# PCB.net
KiCad netlist of a schematic drawn in EAGLE
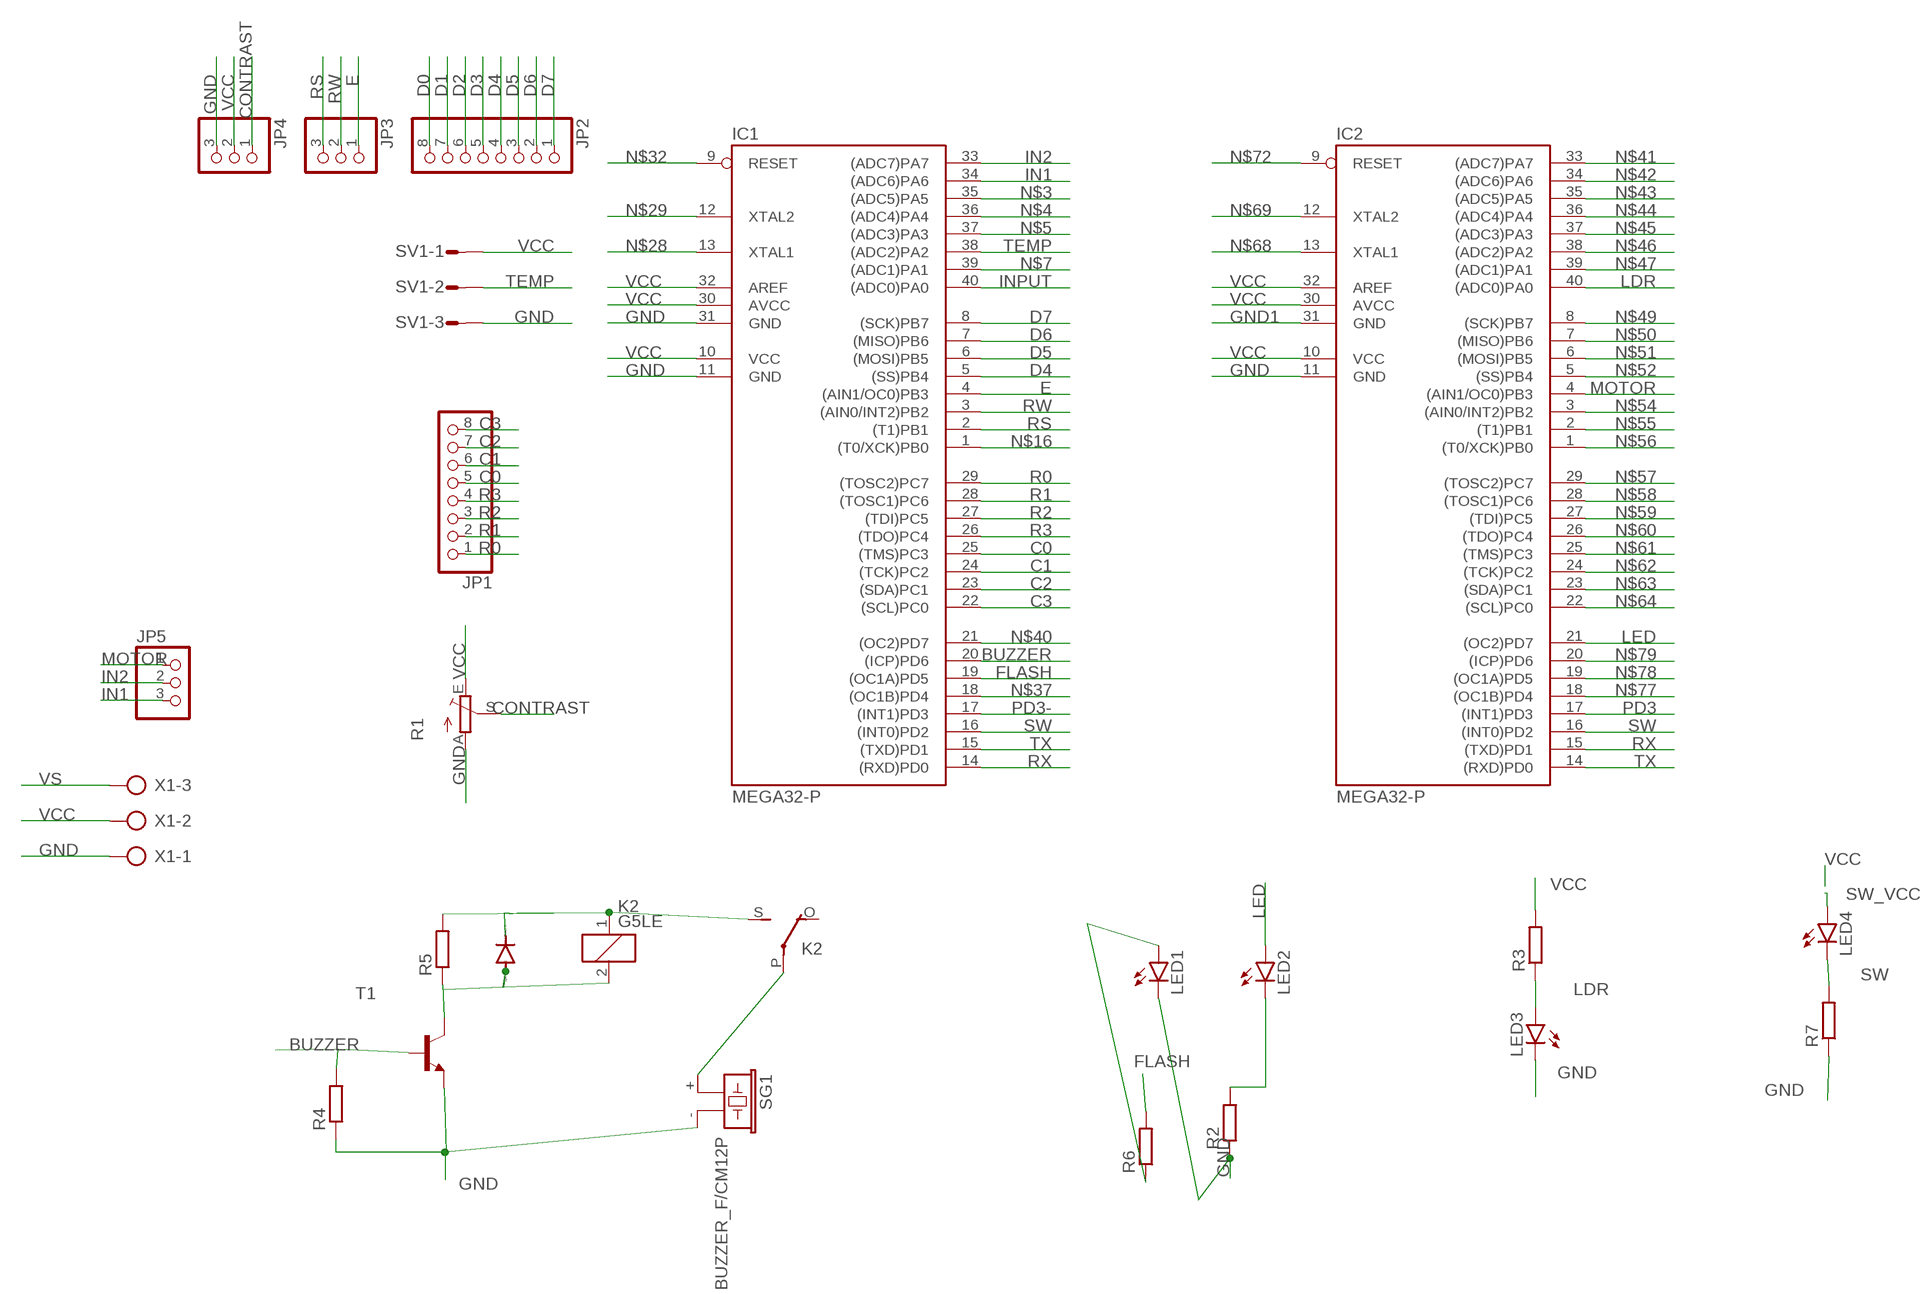
[diagram p0: schematic, sheet 1]

(export (version "E")
  (design (tool "Eeschema 10.0.6"))
  (components
    (comp (ref "D1")
      (value "1N4004")
      (footprint "eagle-import:DO41-10")
      (libsource (lib "eagle-import") (part "1N4004"))
    )
    (comp (ref "IC1")
      (value "MEGA32-P")
      (footprint "eagle-import:DIL40")
      (fields (field (name "MPN") "ATMEGA32-16PU"))
      (libsource (lib "eagle-import") (part "MEGA32-P"))
    )
    (comp (ref "IC2")
      (value "MEGA32-P")
      (footprint "eagle-import:DIL40")
      (fields (field (name "MPN") "ATMEGA32-16PU"))
      (libsource (lib "eagle-import") (part "MEGA32-P"))
    )
    (comp (ref "JP1")
      (value "PINHD-1X8")
      (footprint "eagle-import:1X08")
      (libsource (lib "eagle-import") (part "PINHD-1X8"))
    )
    (comp (ref "JP2")
      (value "PINHD-1X8")
      (footprint "eagle-import:1X08")
      (libsource (lib "eagle-import") (part "PINHD-1X8"))
    )
    (comp (ref "JP3")
      (value "PINHD-1X3")
      (footprint "eagle-import:1X03")
      (libsource (lib "eagle-import") (part "PINHD-1X3"))
    )
    (comp (ref "JP4")
      (value "PINHD-1X3")
      (footprint "eagle-import:1X03")
      (libsource (lib "eagle-import") (part "PINHD-1X3"))
    )
    (comp (ref "JP5")
      (value "PINHD-1X3")
      (footprint "eagle-import:1X03")
      (libsource (lib "eagle-import") (part "PINHD-1X3"))
    )
    (comp (ref "K2")
      (value "G5LE")
      (footprint "eagle-import:G5LE")
      (libsource (lib "eagle-import") (part "G5LE"))
    )
    (comp (ref "LED1")
      (value "LED3MM")
      (footprint "eagle-import:LED3MM")
      (libsource (lib "eagle-import") (part "LED3MM"))
    )
    (comp (ref "LED2")
      (value "LED3MM")
      (footprint "eagle-import:LED3MM")
      (libsource (lib "eagle-import") (part "LED3MM"))
    )
    (comp (ref "LED3")
      (value "LED5MM")
      (footprint "eagle-import:LED5MM")
      (libsource (lib "eagle-import") (part "LED5MM"))
    )
    (comp (ref "LED4")
      (value "LED5MM")
      (footprint "eagle-import:LED5MM")
      (libsource (lib "eagle-import") (part "LED5MM"))
    )
    (comp (ref "R1")
      (value "TRIM_EU-RJ9W")
      (footprint "eagle-import:RJ9W")
      (libsource (lib "eagle-import") (part "TRIM_EU-RJ9W"))
    )
    (comp (ref "R2")
      (value "R-EU_0204/7")
      (footprint "eagle-import:0204_7")
      (libsource (lib "eagle-import") (part "R-EU_0204/7"))
    )
    (comp (ref "R3")
      (value "R-EU_0204/7")
      (footprint "eagle-import:0204_7")
      (libsource (lib "eagle-import") (part "R-EU_0204/7"))
    )
    (comp (ref "R4")
      (value "R-EU_0204/7")
      (footprint "eagle-import:0204_7")
      (libsource (lib "eagle-import") (part "R-EU_0204/7"))
    )
    (comp (ref "R5")
      (value "R-EU_0204/7")
      (footprint "eagle-import:0204_7")
      (libsource (lib "eagle-import") (part "R-EU_0204/7"))
    )
    (comp (ref "R6")
      (value "R-EU_0204/7")
      (footprint "eagle-import:0204_7")
      (libsource (lib "eagle-import") (part "R-EU_0204/7"))
    )
    (comp (ref "R7")
      (value "R-EU_0204/7")
      (footprint "eagle-import:0204_7")
      (libsource (lib "eagle-import") (part "R-EU_0204/7"))
    )
    (comp (ref "SG1")
      (value "BUZZER_F/CM12P")
      (footprint "eagle-import:BUZZER_F_CM12P")
      (libsource (lib "eagle-import") (part "BUZZER_F/CM12P"))
    )
    (comp (ref "SV1")
      (value "CON-AMP-MT_S03P")
      (footprint "eagle-import:CON-AMP-MT_S03P")
      (libsource (lib "eagle-import") (part "CON-AMP-MT_S03P"))
    )
    (comp (ref "T1")
      (value "2N2222-NPN-TO92-EBC")
      (footprint "eagle-import:TO92-EBC")
      (libsource (lib "eagle-import") (part "-NPN-TO92-EBC2N2222"))
    )
    (comp (ref "X1")
      (value "AK300/3")
      (footprint "eagle-import:AK300_3")
      (libsource (lib "eagle-import") (part "AK300/3"))
    )
  )
  (nets
    (net (code "1") (name "/BUZZER") (class "Default")
      (node (ref "IC1") (pin "20") (pinfunction "(ICP)PD6_20") (pintype "bidirectional"))
    )
    (net (code "2") (name "/C0") (class "Default")
      (node (ref "IC1") (pin "25") (pinfunction "(TMS)PC3_25") (pintype "bidirectional"))
      (node (ref "JP1") (pin "5") (pinfunction "5_5") (pintype "passive"))
    )
    (net (code "3") (name "/C1") (class "Default")
      (node (ref "IC1") (pin "24") (pinfunction "(TCK)PC2_24") (pintype "bidirectional"))
      (node (ref "JP1") (pin "6") (pinfunction "6_6") (pintype "passive"))
    )
    (net (code "4") (name "/C2") (class "Default")
      (node (ref "IC1") (pin "23") (pinfunction "(SDA)PC1_23") (pintype "bidirectional"))
      (node (ref "JP1") (pin "7") (pinfunction "7_7") (pintype "passive"))
    )
    (net (code "5") (name "/C3") (class "Default")
      (node (ref "IC1") (pin "22") (pinfunction "(SCL)PC0_22") (pintype "bidirectional"))
      (node (ref "JP1") (pin "8") (pinfunction "8_8") (pintype "passive"))
    )
    (net (code "6") (name "/CONTRAST") (class "Default")
      (node (ref "JP4") (pin "1") (pinfunction "1_1") (pintype "passive"))
      (node (ref "R1") (pin "S") (pinfunction "S_S") (pintype "passive"))
    )
    (net (code "7") (name "/D0") (class "Default")
      (node (ref "JP2") (pin "8") (pinfunction "8_8") (pintype "passive"))
    )
    (net (code "8") (name "/D1") (class "Default")
      (node (ref "JP2") (pin "7") (pinfunction "7_7") (pintype "passive"))
    )
    (net (code "9") (name "/D2") (class "Default")
      (node (ref "JP2") (pin "6") (pinfunction "6_6") (pintype "passive"))
    )
    (net (code "10") (name "/D3") (class "Default")
      (node (ref "JP2") (pin "5") (pinfunction "5_5") (pintype "passive"))
    )
    (net (code "11") (name "/D4") (class "Default")
      (node (ref "IC1") (pin "5") (pinfunction "(SS)PB4_5") (pintype "bidirectional"))
      (node (ref "JP2") (pin "4") (pinfunction "4_4") (pintype "passive"))
    )
    (net (code "12") (name "/D5") (class "Default")
      (node (ref "IC1") (pin "6") (pinfunction "(MOSI)PB5_6") (pintype "bidirectional"))
      (node (ref "JP2") (pin "3") (pinfunction "3_3") (pintype "passive"))
    )
    (net (code "13") (name "/D6") (class "Default")
      (node (ref "IC1") (pin "7") (pinfunction "(MISO)PB6_7") (pintype "bidirectional"))
      (node (ref "JP2") (pin "2") (pinfunction "2_2") (pintype "passive"))
    )
    (net (code "14") (name "/D7") (class "Default")
      (node (ref "IC1") (pin "8") (pinfunction "(SCK)PB7_8") (pintype "bidirectional"))
      (node (ref "JP2") (pin "1") (pinfunction "1_1") (pintype "passive"))
    )
    (net (code "15") (name "/E") (class "Default")
      (node (ref "IC1") (pin "4") (pinfunction "(AIN1/OC0)PB3_4") (pintype "bidirectional"))
      (node (ref "JP3") (pin "1") (pinfunction "1_1") (pintype "passive"))
    )
    (net (code "16") (name "/FLASH") (class "Default")
      (node (ref "IC1") (pin "19") (pinfunction "(OC1A)PD5_19") (pintype "bidirectional"))
      (node (ref "R6") (pin "2") (pinfunction "2_2") (pintype "passive"))
    )
    (net (code "17") (name "/GND") (class "Default")
      (node (ref "IC1") (pin "11") (pinfunction "GND_11") (pintype "power_in"))
      (node (ref "IC1") (pin "31") (pinfunction "GND_31") (pintype "power_in"))
      (node (ref "IC2") (pin "11") (pinfunction "GND_11") (pintype "power_in"))
      (node (ref "JP4") (pin "3") (pinfunction "3_3") (pintype "passive"))
      (node (ref "LED1") (pin "K") (pinfunction "C_K") (pintype "passive"))
      (node (ref "LED3") (pin "K") (pinfunction "C_K") (pintype "passive"))
      (node (ref "R1") (pin "A") (pinfunction "A_A") (pintype "passive"))
      (node (ref "R2") (pin "1") (pinfunction "1_1") (pintype "passive"))
      (node (ref "R4") (pin "1") (pinfunction "1_1") (pintype "passive"))
      (node (ref "R7") (pin "1") (pinfunction "1_1") (pintype "passive"))
      (node (ref "SG1") (pin "-") (pinfunction "2_-") (pintype "passive"))
      (node (ref "SV1") (pin "3") (pinfunction "S_3") (pintype "passive"))
      (node (ref "T1") (pin "E") (pinfunction "E_E") (pintype "passive"))
      (node (ref "X1") (pin "1") (pinfunction "KL_1") (pintype "passive"))
    )
    (net (code "18") (name "/GND1") (class "Default")
      (node (ref "IC2") (pin "31") (pinfunction "GND_31") (pintype "power_in"))
    )
    (net (code "19") (name "/IN1") (class "Default")
      (node (ref "IC1") (pin "34") (pinfunction "(ADC6)PA6_34") (pintype "bidirectional"))
      (node (ref "JP5") (pin "3") (pinfunction "3_3") (pintype "passive"))
    )
    (net (code "20") (name "/IN2") (class "Default")
      (node (ref "IC1") (pin "33") (pinfunction "(ADC7)PA7_33") (pintype "bidirectional"))
      (node (ref "JP5") (pin "2") (pinfunction "2_2") (pintype "passive"))
    )
    (net (code "21") (name "/INPUT") (class "Default")
      (node (ref "IC1") (pin "40") (pinfunction "(ADC0)PA0_40") (pintype "bidirectional"))
    )
    (net (code "22") (name "/LDR") (class "Default")
      (node (ref "IC2") (pin "40") (pinfunction "(ADC0)PA0_40") (pintype "bidirectional"))
      (node (ref "LED3") (pin "A") (pinfunction "A_A") (pintype "passive"))
      (node (ref "R3") (pin "1") (pinfunction "1_1") (pintype "passive"))
    )
    (net (code "23") (name "/LED") (class "Default")
      (node (ref "IC2") (pin "21") (pinfunction "(OC2)PD7_21") (pintype "bidirectional"))
      (node (ref "LED2") (pin "A") (pinfunction "A_A") (pintype "passive"))
    )
    (net (code "24") (name "/MOTOR") (class "Default")
      (node (ref "IC2") (pin "4") (pinfunction "(AIN1/OC0)PB3_4") (pintype "bidirectional"))
      (node (ref "JP5") (pin "1") (pinfunction "1_1") (pintype "passive"))
    )
    (net (code "25") (name "/N$3") (class "Default")
      (node (ref "IC1") (pin "35") (pinfunction "(ADC5)PA5_35") (pintype "bidirectional"))
    )
    (net (code "26") (name "/N$4") (class "Default")
      (node (ref "IC1") (pin "36") (pinfunction "(ADC4)PA4_36") (pintype "bidirectional"))
    )
    (net (code "27") (name "/N$5") (class "Default")
      (node (ref "IC1") (pin "37") (pinfunction "(ADC3)PA3_37") (pintype "bidirectional"))
    )
    (net (code "28") (name "/N$7") (class "Default")
      (node (ref "IC1") (pin "39") (pinfunction "(ADC1)PA1_39") (pintype "bidirectional"))
    )
    (net (code "29") (name "/N$16") (class "Default")
      (node (ref "IC1") (pin "1") (pinfunction "(T0/XCK)PB0_1") (pintype "bidirectional"))
    )
    (net (code "30") (name "/N$28") (class "Default")
      (node (ref "IC1") (pin "13") (pinfunction "XTAL1_13") (pintype "bidirectional"))
    )
    (net (code "31") (name "/N$29") (class "Default")
      (node (ref "IC1") (pin "12") (pinfunction "XTAL2_12") (pintype "bidirectional"))
    )
    (net (code "32") (name "/N$32") (class "Default")
      (node (ref "IC1") (pin "9") (pinfunction "RESET_9") (pintype "input"))
    )
    (net (code "33") (name "/N$37") (class "Default")
      (node (ref "IC1") (pin "18") (pinfunction "(OC1B)PD4_18") (pintype "bidirectional"))
    )
    (net (code "34") (name "/N$40") (class "Default")
      (node (ref "IC1") (pin "21") (pinfunction "(OC2)PD7_21") (pintype "bidirectional"))
    )
    (net (code "35") (name "/N$41") (class "Default")
      (node (ref "IC2") (pin "33") (pinfunction "(ADC7)PA7_33") (pintype "bidirectional"))
    )
    (net (code "36") (name "/N$42") (class "Default")
      (node (ref "IC2") (pin "34") (pinfunction "(ADC6)PA6_34") (pintype "bidirectional"))
    )
    (net (code "37") (name "/N$43") (class "Default")
      (node (ref "IC2") (pin "35") (pinfunction "(ADC5)PA5_35") (pintype "bidirectional"))
    )
    (net (code "38") (name "/N$44") (class "Default")
      (node (ref "IC2") (pin "36") (pinfunction "(ADC4)PA4_36") (pintype "bidirectional"))
    )
    (net (code "39") (name "/N$45") (class "Default")
      (node (ref "IC2") (pin "37") (pinfunction "(ADC3)PA3_37") (pintype "bidirectional"))
    )
    (net (code "40") (name "/N$46") (class "Default")
      (node (ref "IC2") (pin "38") (pinfunction "(ADC2)PA2_38") (pintype "bidirectional"))
    )
    (net (code "41") (name "/N$47") (class "Default")
      (node (ref "IC2") (pin "39") (pinfunction "(ADC1)PA1_39") (pintype "bidirectional"))
    )
    (net (code "42") (name "/N$49") (class "Default")
      (node (ref "IC2") (pin "8") (pinfunction "(SCK)PB7_8") (pintype "bidirectional"))
    )
    (net (code "43") (name "/N$50") (class "Default")
      (node (ref "IC2") (pin "7") (pinfunction "(MISO)PB6_7") (pintype "bidirectional"))
    )
    (net (code "44") (name "/N$51") (class "Default")
      (node (ref "IC2") (pin "6") (pinfunction "(MOSI)PB5_6") (pintype "bidirectional"))
    )
    (net (code "45") (name "/N$52") (class "Default")
      (node (ref "IC2") (pin "5") (pinfunction "(SS)PB4_5") (pintype "bidirectional"))
    )
    (net (code "46") (name "/N$54") (class "Default")
      (node (ref "IC2") (pin "3") (pinfunction "(AIN0/INT2)PB2_3") (pintype "bidirectional"))
    )
    (net (code "47") (name "/N$55") (class "Default")
      (node (ref "IC2") (pin "2") (pinfunction "(T1)PB1_2") (pintype "bidirectional"))
    )
    (net (code "48") (name "/N$56") (class "Default")
      (node (ref "IC2") (pin "1") (pinfunction "(T0/XCK)PB0_1") (pintype "bidirectional"))
    )
    (net (code "49") (name "/N$57") (class "Default")
      (node (ref "IC2") (pin "29") (pinfunction "(TOSC2)PC7_29") (pintype "bidirectional"))
    )
    (net (code "50") (name "/N$58") (class "Default")
      (node (ref "IC2") (pin "28") (pinfunction "(TOSC1)PC6_28") (pintype "bidirectional"))
    )
    (net (code "51") (name "/N$59") (class "Default")
      (node (ref "IC2") (pin "27") (pinfunction "(TDI)PC5_27") (pintype "bidirectional"))
    )
    (net (code "52") (name "/N$60") (class "Default")
      (node (ref "IC2") (pin "26") (pinfunction "(TDO)PC4_26") (pintype "bidirectional"))
    )
    (net (code "53") (name "/N$61") (class "Default")
      (node (ref "IC2") (pin "25") (pinfunction "(TMS)PC3_25") (pintype "bidirectional"))
    )
    (net (code "54") (name "/N$62") (class "Default")
      (node (ref "IC2") (pin "24") (pinfunction "(TCK)PC2_24") (pintype "bidirectional"))
    )
    (net (code "55") (name "/N$63") (class "Default")
      (node (ref "IC2") (pin "23") (pinfunction "(SDA)PC1_23") (pintype "bidirectional"))
    )
    (net (code "56") (name "/N$64") (class "Default")
      (node (ref "IC2") (pin "22") (pinfunction "(SCL)PC0_22") (pintype "bidirectional"))
    )
    (net (code "57") (name "/N$68") (class "Default")
      (node (ref "IC2") (pin "13") (pinfunction "XTAL1_13") (pintype "bidirectional"))
    )
    (net (code "58") (name "/N$69") (class "Default")
      (node (ref "IC2") (pin "12") (pinfunction "XTAL2_12") (pintype "bidirectional"))
    )
    (net (code "59") (name "/N$72") (class "Default")
      (node (ref "IC2") (pin "9") (pinfunction "RESET_9") (pintype "input"))
    )
    (net (code "60") (name "/N$77") (class "Default")
      (node (ref "IC2") (pin "18") (pinfunction "(OC1B)PD4_18") (pintype "bidirectional"))
    )
    (net (code "61") (name "/N$78") (class "Default")
      (node (ref "IC2") (pin "19") (pinfunction "(OC1A)PD5_19") (pintype "bidirectional"))
    )
    (net (code "62") (name "/N$79") (class "Default")
      (node (ref "IC2") (pin "20") (pinfunction "(ICP)PD6_20") (pintype "bidirectional"))
    )
    (net (code "63") (name "/PD3") (class "Default")
      (node (ref "IC2") (pin "17") (pinfunction "(INT1)PD3_17") (pintype "bidirectional"))
    )
    (net (code "64") (name "/PD3-") (class "Default")
      (node (ref "IC1") (pin "17") (pinfunction "(INT1)PD3_17") (pintype "bidirectional"))
    )
    (net (code "65") (name "/R0") (class "Default")
      (node (ref "IC1") (pin "29") (pinfunction "(TOSC2)PC7_29") (pintype "bidirectional"))
      (node (ref "JP1") (pin "1") (pinfunction "1_1") (pintype "passive"))
    )
    (net (code "66") (name "/R1") (class "Default")
      (node (ref "IC1") (pin "28") (pinfunction "(TOSC1)PC6_28") (pintype "bidirectional"))
      (node (ref "JP1") (pin "2") (pinfunction "2_2") (pintype "passive"))
    )
    (net (code "67") (name "/R2") (class "Default")
      (node (ref "IC1") (pin "27") (pinfunction "(TDI)PC5_27") (pintype "bidirectional"))
      (node (ref "JP1") (pin "3") (pinfunction "3_3") (pintype "passive"))
    )
    (net (code "68") (name "/R3") (class "Default")
      (node (ref "IC1") (pin "26") (pinfunction "(TDO)PC4_26") (pintype "bidirectional"))
      (node (ref "JP1") (pin "4") (pinfunction "4_4") (pintype "passive"))
    )
    (net (code "69") (name "/RS") (class "Default")
      (node (ref "IC1") (pin "2") (pinfunction "(T1)PB1_2") (pintype "bidirectional"))
      (node (ref "JP3") (pin "3") (pinfunction "3_3") (pintype "passive"))
    )
    (net (code "70") (name "/RW") (class "Default")
      (node (ref "IC1") (pin "3") (pinfunction "(AIN0/INT2)PB2_3") (pintype "bidirectional"))
      (node (ref "JP3") (pin "2") (pinfunction "2_2") (pintype "passive"))
    )
    (net (code "71") (name "/RX") (class "Default")
      (node (ref "IC1") (pin "14") (pinfunction "(RXD)PD0_14") (pintype "bidirectional"))
      (node (ref "IC2") (pin "15") (pinfunction "(TXD)PD1_15") (pintype "bidirectional"))
    )
    (net (code "72") (name "/SW") (class "Default")
      (node (ref "IC1") (pin "16") (pinfunction "(INT0)PD2_16") (pintype "bidirectional"))
      (node (ref "IC2") (pin "16") (pinfunction "(INT0)PD2_16") (pintype "bidirectional"))
      (node (ref "LED4") (pin "K") (pinfunction "C_K") (pintype "passive"))
      (node (ref "R7") (pin "2") (pinfunction "2_2") (pintype "passive"))
    )
    (net (code "73") (name "/SW_VCC") (class "Default")
      (node (ref "LED4") (pin "A") (pinfunction "A_A") (pintype "passive"))
    )
    (net (code "74") (name "/TEMP") (class "Default")
      (node (ref "IC1") (pin "38") (pinfunction "(ADC2)PA2_38") (pintype "bidirectional"))
      (node (ref "SV1") (pin "2") (pinfunction "S_2") (pintype "passive"))
    )
    (net (code "75") (name "/TX") (class "Default")
      (node (ref "IC1") (pin "15") (pinfunction "(TXD)PD1_15") (pintype "bidirectional"))
      (node (ref "IC2") (pin "14") (pinfunction "(RXD)PD0_14") (pintype "bidirectional"))
    )
    (net (code "76") (name "/VCC") (class "Default")
      (node (ref "IC1") (pin "10") (pinfunction "VCC_10") (pintype "power_in"))
      (node (ref "IC1") (pin "30") (pinfunction "AVCC_30") (pintype "power_in"))
      (node (ref "IC1") (pin "32") (pinfunction "AREF_32") (pintype "passive"))
      (node (ref "IC2") (pin "10") (pinfunction "VCC_10") (pintype "power_in"))
      (node (ref "IC2") (pin "30") (pinfunction "AVCC_30") (pintype "power_in"))
      (node (ref "IC2") (pin "32") (pinfunction "AREF_32") (pintype "passive"))
      (node (ref "JP4") (pin "2") (pinfunction "2_2") (pintype "passive"))
      (node (ref "R1") (pin "E") (pinfunction "E_E") (pintype "passive"))
      (node (ref "R3") (pin "2") (pinfunction "2_2") (pintype "passive"))
      (node (ref "SV1") (pin "1") (pinfunction "S_1") (pintype "passive"))
      (node (ref "X1") (pin "2") (pinfunction "KL_2") (pintype "passive"))
    )
    (net (code "77") (name "/VS") (class "Default")
      (node (ref "X1") (pin "3") (pinfunction "KL_3") (pintype "passive"))
    )
    (net (code "78") (name "Net-(D1-PadA)") (class "Default")
      (node (ref "D1") (pin "A") (pinfunction "A_A") (pintype "passive"))
      (node (ref "K2") (pin "2") (pinfunction "2_2") (pintype "passive"))
    )
    (net (code "79") (name "Net-(D1-PadC)") (class "Default")
      (node (ref "D1") (pin "C") (pinfunction "C_C") (pintype "passive"))
      (node (ref "K2") (pin "1") (pinfunction "1_1") (pintype "passive"))
      (node (ref "K2") (pin "S") (pinfunction "S_S") (pintype "passive"))
      (node (ref "R5") (pin "2") (pinfunction "2_2") (pintype "passive"))
    )
    (net (code "80") (name "Net-(LED1-PadA)") (class "Default")
      (node (ref "LED1") (pin "A") (pinfunction "A_A") (pintype "passive"))
      (node (ref "R6") (pin "1") (pinfunction "1_1") (pintype "passive"))
    )
    (net (code "81") (name "Net-(LED2-C)") (class "Default")
      (node (ref "LED2") (pin "K") (pinfunction "C_K") (pintype "passive"))
      (node (ref "R2") (pin "2") (pinfunction "2_2") (pintype "passive"))
    )
    (net (code "82") (name "Net-(R4-Pad2)") (class "Default")
      (node (ref "R4") (pin "2") (pinfunction "2_2") (pintype "passive"))
      (node (ref "T1") (pin "B") (pinfunction "B_B") (pintype "passive"))
    )
    (net (code "83") (name "Net-(R5-Pad1)") (class "Default")
      (node (ref "R5") (pin "1") (pinfunction "1_1") (pintype "passive"))
      (node (ref "T1") (pin "C") (pinfunction "C_C") (pintype "passive"))
    )
    (net (code "84") (name "Net-(SG1-1)") (class "Default")
      (node (ref "K2") (pin "P") (pinfunction "P_P") (pintype "passive"))
      (node (ref "SG1") (pin "+") (pinfunction "1_+") (pintype "passive"))
    )
    (net (code "85") (name "unconnected-(K2-PadO)") (class "Default")
      (node (ref "K2") (pin "O") (pinfunction "O_O") (pintype "passive"))
    )
  )
)
